# schema_8relay.net
KiCad netlist of a schematic drawn in EAGLE
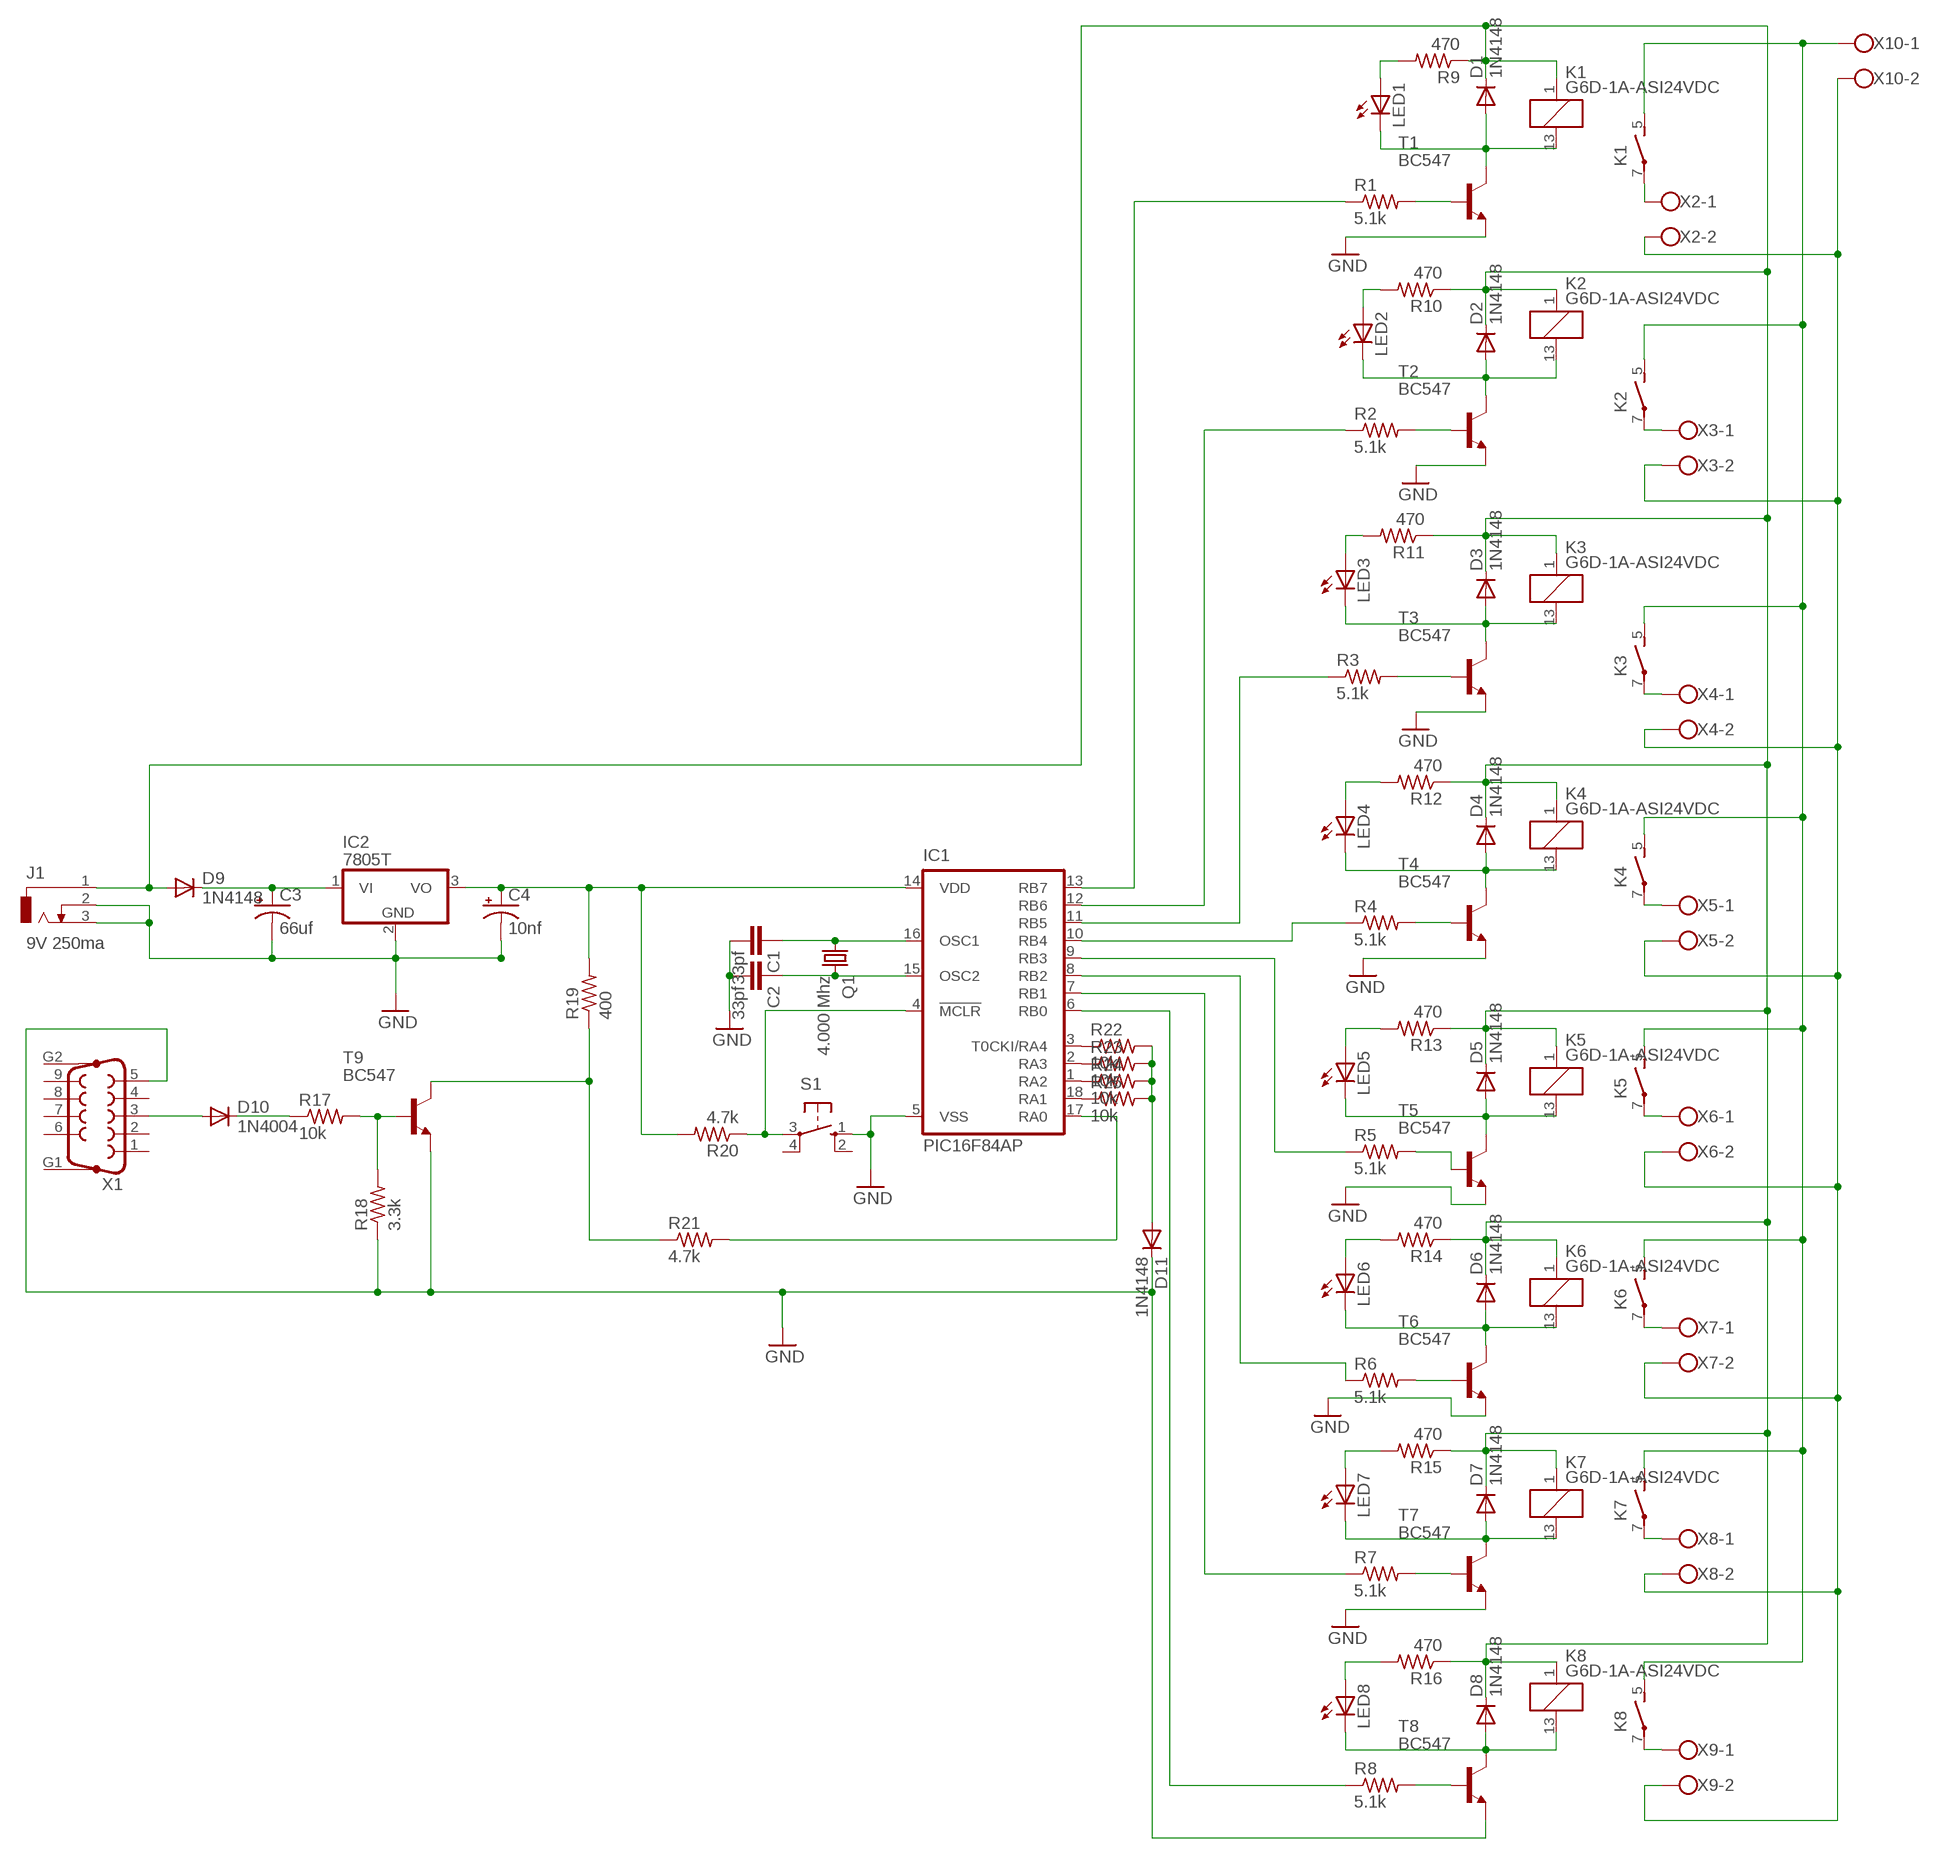
[diagram p0: schematic, sheet 1]

(export (version "E")
  (design (tool "Eeschema 10.0.6"))
  (components
    (comp (ref "C1")
      (value "33pf")
      (footprint "eagle-import:C050-024X044")
      (libsource (lib "eagle-import") (part "C-EU050-024X044"))
    )
    (comp (ref "C2")
      (value "33pf")
      (footprint "eagle-import:C050-024X044")
      (libsource (lib "eagle-import") (part "C-EU050-024X044"))
    )
    (comp (ref "C3")
      (value "66uf")
      (footprint "eagle-import:E2,5-6")
      (libsource (lib "eagle-import") (part "CPOL-USE2.5-6"))
    )
    (comp (ref "C4")
      (value "10nf")
      (footprint "eagle-import:E2,5-6")
      (libsource (lib "eagle-import") (part "CPOL-USE2.5-6"))
    )
    (comp (ref "D1")
      (value "1N4148")
      (footprint "eagle-import:DO35-10")
      (libsource (lib "eagle-import") (part "1N4148"))
    )
    (comp (ref "D2")
      (value "1N4148")
      (footprint "eagle-import:DO35-10")
      (libsource (lib "eagle-import") (part "1N4148"))
    )
    (comp (ref "D3")
      (value "1N4148")
      (footprint "eagle-import:DO35-10")
      (libsource (lib "eagle-import") (part "1N4148"))
    )
    (comp (ref "D4")
      (value "1N4148")
      (footprint "eagle-import:DO35-10")
      (libsource (lib "eagle-import") (part "1N4148"))
    )
    (comp (ref "D5")
      (value "1N4148")
      (footprint "eagle-import:DO35-10")
      (libsource (lib "eagle-import") (part "1N4148"))
    )
    (comp (ref "D6")
      (value "1N4148")
      (footprint "eagle-import:DO35-10")
      (libsource (lib "eagle-import") (part "1N4148"))
    )
    (comp (ref "D7")
      (value "1N4148")
      (footprint "eagle-import:DO35-10")
      (libsource (lib "eagle-import") (part "1N4148"))
    )
    (comp (ref "D8")
      (value "1N4148")
      (footprint "eagle-import:DO35-10")
      (libsource (lib "eagle-import") (part "1N4148"))
    )
    (comp (ref "D9")
      (value "1N4148")
      (footprint "eagle-import:DO35-10")
      (libsource (lib "eagle-import") (part "1N4148"))
    )
    (comp (ref "D10")
      (value "1N4004")
      (footprint "eagle-import:DO41-10")
      (libsource (lib "eagle-import") (part "1N4004"))
    )
    (comp (ref "D11")
      (value "1N4148")
      (footprint "eagle-import:DO35-10")
      (libsource (lib "eagle-import") (part "1N4148"))
    )
    (comp (ref "IC1")
      (value "PIC16F84AP")
      (footprint "eagle-import:DIL18")
      (libsource (lib "eagle-import") (part "PIC16F8P4A"))
    )
    (comp (ref "IC2")
      (value "7805T")
      (footprint "eagle-import:TO220H")
      (libsource (lib "eagle-import") (part "78T05"))
    )
    (comp (ref "J1")
      (value "9V 250ma")
      (footprint "eagle-import:DCJ0303")
      (libsource (lib "eagle-import") (part "DCJ0303"))
    )
    (comp (ref "K1")
      (value "G6D-1A-ASI24VDC")
      (footprint "eagle-import:G6D")
      (libsource (lib "eagle-import") (part "G6D?-1A-ASI24VDC"))
    )
    (comp (ref "K2")
      (value "G6D-1A-ASI24VDC")
      (footprint "eagle-import:G6D")
      (libsource (lib "eagle-import") (part "G6D?-1A-ASI24VDC"))
    )
    (comp (ref "K3")
      (value "G6D-1A-ASI24VDC")
      (footprint "eagle-import:G6D")
      (libsource (lib "eagle-import") (part "G6D?-1A-ASI24VDC"))
    )
    (comp (ref "K4")
      (value "G6D-1A-ASI24VDC")
      (footprint "eagle-import:G6D")
      (libsource (lib "eagle-import") (part "G6D?-1A-ASI24VDC"))
    )
    (comp (ref "K5")
      (value "G6D-1A-ASI24VDC")
      (footprint "eagle-import:G6D")
      (libsource (lib "eagle-import") (part "G6D?-1A-ASI24VDC"))
    )
    (comp (ref "K6")
      (value "G6D-1A-ASI24VDC")
      (footprint "eagle-import:G6D")
      (libsource (lib "eagle-import") (part "G6D?-1A-ASI24VDC"))
    )
    (comp (ref "K7")
      (value "G6D-1A-ASI24VDC")
      (footprint "eagle-import:G6D")
      (libsource (lib "eagle-import") (part "G6D?-1A-ASI24VDC"))
    )
    (comp (ref "K8")
      (value "G6D-1A-ASI24VDC")
      (footprint "eagle-import:G6D")
      (libsource (lib "eagle-import") (part "G6D?-1A-ASI24VDC"))
    )
    (comp (ref "LED1")
      (value "LED3MM")
      (footprint "eagle-import:LED3MM")
      (libsource (lib "eagle-import") (part "LED3MM"))
    )
    (comp (ref "LED2")
      (value "LED3MM")
      (footprint "eagle-import:LED3MM")
      (libsource (lib "eagle-import") (part "LED3MM"))
    )
    (comp (ref "LED3")
      (value "LED3MM")
      (footprint "eagle-import:LED3MM")
      (libsource (lib "eagle-import") (part "LED3MM"))
    )
    (comp (ref "LED4")
      (value "LED3MM")
      (footprint "eagle-import:LED3MM")
      (libsource (lib "eagle-import") (part "LED3MM"))
    )
    (comp (ref "LED5")
      (value "LED3MM")
      (footprint "eagle-import:LED3MM")
      (libsource (lib "eagle-import") (part "LED3MM"))
    )
    (comp (ref "LED6")
      (value "LED3MM")
      (footprint "eagle-import:LED3MM")
      (libsource (lib "eagle-import") (part "LED3MM"))
    )
    (comp (ref "LED7")
      (value "LED3MM")
      (footprint "eagle-import:LED3MM")
      (libsource (lib "eagle-import") (part "LED3MM"))
    )
    (comp (ref "LED8")
      (value "LED3MM")
      (footprint "eagle-import:LED3MM")
      (libsource (lib "eagle-import") (part "LED3MM"))
    )
    (comp (ref "Q1")
      (value "4.000 Mhz")
      (footprint "eagle-import:HC49U70")
      (libsource (lib "eagle-import") (part "CRYSTALHC49U70"))
    )
    (comp (ref "R1")
      (value "5.1k")
      (footprint "eagle-import:0204_7")
      (libsource (lib "eagle-import") (part "R-US_0204/7"))
    )
    (comp (ref "R2")
      (value "5.1k")
      (footprint "eagle-import:0204_7")
      (libsource (lib "eagle-import") (part "R-US_0204/7"))
    )
    (comp (ref "R3")
      (value "5.1k")
      (footprint "eagle-import:0204_7")
      (libsource (lib "eagle-import") (part "R-US_0204/7"))
    )
    (comp (ref "R4")
      (value "5.1k")
      (footprint "eagle-import:0204_7")
      (libsource (lib "eagle-import") (part "R-US_0204/7"))
    )
    (comp (ref "R5")
      (value "5.1k")
      (footprint "eagle-import:0204_7")
      (libsource (lib "eagle-import") (part "R-US_0204/7"))
    )
    (comp (ref "R6")
      (value "5.1k")
      (footprint "eagle-import:0204_7")
      (libsource (lib "eagle-import") (part "R-US_0204/7"))
    )
    (comp (ref "R7")
      (value "5.1k")
      (footprint "eagle-import:0204_7")
      (libsource (lib "eagle-import") (part "R-US_0204/7"))
    )
    (comp (ref "R8")
      (value "5.1k")
      (footprint "eagle-import:0204_7")
      (libsource (lib "eagle-import") (part "R-US_0204/7"))
    )
    (comp (ref "R9")
      (value "470")
      (footprint "eagle-import:0204_7")
      (libsource (lib "eagle-import") (part "R-US_0204/7"))
    )
    (comp (ref "R10")
      (value "470")
      (footprint "eagle-import:0204_7")
      (libsource (lib "eagle-import") (part "R-US_0204/7"))
    )
    (comp (ref "R11")
      (value "470")
      (footprint "eagle-import:0204_7")
      (libsource (lib "eagle-import") (part "R-US_0204/7"))
    )
    (comp (ref "R12")
      (value "470")
      (footprint "eagle-import:0204_7")
      (libsource (lib "eagle-import") (part "R-US_0204/7"))
    )
    (comp (ref "R13")
      (value "470")
      (footprint "eagle-import:0204_7")
      (libsource (lib "eagle-import") (part "R-US_0204/7"))
    )
    (comp (ref "R14")
      (value "470")
      (footprint "eagle-import:0204_7")
      (libsource (lib "eagle-import") (part "R-US_0204/7"))
    )
    (comp (ref "R15")
      (value "470")
      (footprint "eagle-import:0204_7")
      (libsource (lib "eagle-import") (part "R-US_0204/7"))
    )
    (comp (ref "R16")
      (value "470")
      (footprint "eagle-import:0204_7")
      (libsource (lib "eagle-import") (part "R-US_0204/7"))
    )
    (comp (ref "R17")
      (value "10k")
      (footprint "eagle-import:0204_7")
      (libsource (lib "eagle-import") (part "R-US_0204/7"))
    )
    (comp (ref "R18")
      (value "3.3k")
      (footprint "eagle-import:0204_7")
      (libsource (lib "eagle-import") (part "R-US_0204/7"))
    )
    (comp (ref "R19")
      (value "400")
      (footprint "eagle-import:0207_12")
      (libsource (lib "eagle-import") (part "R-US_0207/12"))
    )
    (comp (ref "R20")
      (value "4.7k")
      (footprint "eagle-import:0204_7")
      (libsource (lib "eagle-import") (part "R-US_0204/7"))
    )
    (comp (ref "R21")
      (value "4.7k")
      (footprint "eagle-import:0204_7")
      (libsource (lib "eagle-import") (part "R-US_0204/7"))
    )
    (comp (ref "R22")
      (value "10k")
      (footprint "eagle-import:0204_7")
      (libsource (lib "eagle-import") (part "R-US_0204/7"))
    )
    (comp (ref "R23")
      (value "10k")
      (footprint "eagle-import:0204_7")
      (libsource (lib "eagle-import") (part "R-US_0204/7"))
    )
    (comp (ref "R24")
      (value "10k")
      (footprint "eagle-import:0204_7")
      (libsource (lib "eagle-import") (part "R-US_0204/7"))
    )
    (comp (ref "R25")
      (value "10k")
      (footprint "eagle-import:0204_7")
      (libsource (lib "eagle-import") (part "R-US_0204/7"))
    )
    (comp (ref "S1")
      (value "10-XX")
      (footprint "eagle-import:B3F-10XX")
      (libsource (lib "eagle-import") (part "10-XX"))
    )
    (comp (ref "T1")
      (value "BC547")
      (footprint "eagle-import:TO92")
      (libsource (lib "eagle-import") (part "BC547"))
    )
    (comp (ref "T2")
      (value "BC547")
      (footprint "eagle-import:TO92")
      (libsource (lib "eagle-import") (part "BC547"))
    )
    (comp (ref "T3")
      (value "BC547")
      (footprint "eagle-import:TO92")
      (libsource (lib "eagle-import") (part "BC547"))
    )
    (comp (ref "T4")
      (value "BC547")
      (footprint "eagle-import:TO92")
      (libsource (lib "eagle-import") (part "BC547"))
    )
    (comp (ref "T5")
      (value "BC547")
      (footprint "eagle-import:TO92")
      (libsource (lib "eagle-import") (part "BC547"))
    )
    (comp (ref "T6")
      (value "BC547")
      (footprint "eagle-import:TO92")
      (libsource (lib "eagle-import") (part "BC547"))
    )
    (comp (ref "T7")
      (value "BC547")
      (footprint "eagle-import:TO92")
      (libsource (lib "eagle-import") (part "BC547"))
    )
    (comp (ref "T8")
      (value "BC547")
      (footprint "eagle-import:TO92")
      (libsource (lib "eagle-import") (part "BC547"))
    )
    (comp (ref "T9")
      (value "BC547")
      (footprint "eagle-import:TO92")
      (libsource (lib "eagle-import") (part "BC547"))
    )
    (comp (ref "X1")
      (value "F09HP")
      (footprint "eagle-import:F09HP")
      (libsource (lib "eagle-import") (part "F09HP"))
    )
    (comp (ref "X2")
      (value "W237-102")
      (footprint "eagle-import:W237-102")
      (libsource (lib "eagle-import") (part "W237-102"))
    )
    (comp (ref "X3")
      (value "W237-102")
      (footprint "eagle-import:W237-102")
      (libsource (lib "eagle-import") (part "W237-102"))
    )
    (comp (ref "X4")
      (value "W237-102")
      (footprint "eagle-import:W237-102")
      (libsource (lib "eagle-import") (part "W237-102"))
    )
    (comp (ref "X5")
      (value "W237-102")
      (footprint "eagle-import:W237-102")
      (libsource (lib "eagle-import") (part "W237-102"))
    )
    (comp (ref "X6")
      (value "W237-102")
      (footprint "eagle-import:W237-102")
      (libsource (lib "eagle-import") (part "W237-102"))
    )
    (comp (ref "X7")
      (value "W237-102")
      (footprint "eagle-import:W237-102")
      (libsource (lib "eagle-import") (part "W237-102"))
    )
    (comp (ref "X8")
      (value "W237-102")
      (footprint "eagle-import:W237-102")
      (libsource (lib "eagle-import") (part "W237-102"))
    )
    (comp (ref "X9")
      (value "W237-102")
      (footprint "eagle-import:W237-102")
      (libsource (lib "eagle-import") (part "W237-102"))
    )
    (comp (ref "X10")
      (value "W237-102")
      (footprint "eagle-import:W237-102")
      (libsource (lib "eagle-import") (part "W237-102"))
    )
  )
  (nets
    (net (code "1") (name "GND") (class "Default")
      (node (ref "C1") (pin "2") (pinfunction "2_2") (pintype "passive"))
      (node (ref "C2") (pin "2") (pinfunction "2_2") (pintype "passive"))
      (node (ref "C3") (pin "-") (pinfunction "-_-") (pintype "passive"))
      (node (ref "C4") (pin "-") (pinfunction "-_-") (pintype "passive"))
      (node (ref "D11") (pin "C") (pinfunction "C_C") (pintype "passive"))
      (node (ref "IC1") (pin "5") (pinfunction "VSS_5") (pintype "power_in"))
      (node (ref "IC2") (pin "2") (pinfunction "GND_2") (pintype "passive"))
      (node (ref "J1") (pin "2") (pinfunction "2_2") (pintype "passive"))
      (node (ref "J1") (pin "3") (pinfunction "3_3") (pintype "passive"))
      (node (ref "R18") (pin "1") (pinfunction "1_1") (pintype "passive"))
      (node (ref "S1") (pin "1") (pinfunction "S_1") (pintype "passive"))
      (node (ref "T1") (pin "1") (pinfunction "E_1") (pintype "passive"))
      (node (ref "T2") (pin "1") (pinfunction "E_1") (pintype "passive"))
      (node (ref "T3") (pin "1") (pinfunction "E_1") (pintype "passive"))
      (node (ref "T4") (pin "1") (pinfunction "E_1") (pintype "passive"))
      (node (ref "T5") (pin "1") (pinfunction "E_1") (pintype "passive"))
      (node (ref "T6") (pin "1") (pinfunction "E_1") (pintype "passive"))
      (node (ref "T7") (pin "1") (pinfunction "E_1") (pintype "passive"))
      (node (ref "T8") (pin "1") (pinfunction "E_1") (pintype "passive"))
      (node (ref "T9") (pin "1") (pinfunction "E_1") (pintype "passive"))
      (node (ref "X1") (pin "5") (pinfunction "5_5") (pintype "passive"))
    )
    (net (code "2") (name "Net-(D1-PadC)") (class "Default")
      (node (ref "D1") (pin "C") (pinfunction "C_C") (pintype "passive"))
      (node (ref "D2") (pin "C") (pinfunction "C_C") (pintype "passive"))
      (node (ref "D3") (pin "C") (pinfunction "C_C") (pintype "passive"))
      (node (ref "D4") (pin "C") (pinfunction "C_C") (pintype "passive"))
      (node (ref "D5") (pin "C") (pinfunction "C_C") (pintype "passive"))
      (node (ref "D6") (pin "C") (pinfunction "C_C") (pintype "passive"))
      (node (ref "D7") (pin "C") (pinfunction "C_C") (pintype "passive"))
      (node (ref "D8") (pin "C") (pinfunction "C_C") (pintype "passive"))
      (node (ref "D9") (pin "A") (pinfunction "A_A") (pintype "passive"))
      (node (ref "J1") (pin "1") (pinfunction "1_1") (pintype "passive"))
      (node (ref "K1") (pin "1") (pinfunction "1_1") (pintype "passive"))
      (node (ref "K2") (pin "1") (pinfunction "1_1") (pintype "passive"))
      (node (ref "K3") (pin "1") (pinfunction "1_1") (pintype "passive"))
      (node (ref "K4") (pin "1") (pinfunction "1_1") (pintype "passive"))
      (node (ref "K5") (pin "1") (pinfunction "1_1") (pintype "passive"))
      (node (ref "K6") (pin "1") (pinfunction "1_1") (pintype "passive"))
      (node (ref "K7") (pin "1") (pinfunction "1_1") (pintype "passive"))
      (node (ref "K8") (pin "1") (pinfunction "1_1") (pintype "passive"))
      (node (ref "R10") (pin "1") (pinfunction "1_1") (pintype "passive"))
      (node (ref "R11") (pin "1") (pinfunction "1_1") (pintype "passive"))
      (node (ref "R12") (pin "1") (pinfunction "1_1") (pintype "passive"))
      (node (ref "R13") (pin "1") (pinfunction "1_1") (pintype "passive"))
      (node (ref "R14") (pin "1") (pinfunction "1_1") (pintype "passive"))
      (node (ref "R15") (pin "1") (pinfunction "1_1") (pintype "passive"))
      (node (ref "R16") (pin "1") (pinfunction "1_1") (pintype "passive"))
      (node (ref "R9") (pin "1") (pinfunction "1_1") (pintype "passive"))
    )
    (net (code "3") (name "Net-(D10-PadA)") (class "Default")
      (node (ref "D10") (pin "A") (pinfunction "A_A") (pintype "passive"))
      (node (ref "X1") (pin "3") (pinfunction "3_3") (pintype "passive"))
    )
    (net (code "4") (name "Net-(D10-PadC)") (class "Default")
      (node (ref "D10") (pin "C") (pinfunction "C_C") (pintype "passive"))
      (node (ref "R17") (pin "1") (pinfunction "1_1") (pintype "passive"))
    )
    (net (code "5") (name "Net-(D11-PadA)") (class "Default")
      (node (ref "D11") (pin "A") (pinfunction "A_A") (pintype "passive"))
      (node (ref "R22") (pin "2") (pinfunction "2_2") (pintype "passive"))
      (node (ref "R23") (pin "2") (pinfunction "2_2") (pintype "passive"))
      (node (ref "R24") (pin "2") (pinfunction "2_2") (pintype "passive"))
      (node (ref "R25") (pin "2") (pinfunction "2_2") (pintype "passive"))
    )
    (net (code "6") (name "Net-(IC1-OSC1)") (class "Default")
      (node (ref "C1") (pin "1") (pinfunction "1_1") (pintype "passive"))
      (node (ref "IC1") (pin "16") (pinfunction "OSC1_16") (pintype "input"))
      (node (ref "Q1") (pin "1") (pinfunction "1_1") (pintype "passive"))
    )
    (net (code "7") (name "Net-(IC1-OSC2)") (class "Default")
      (node (ref "C2") (pin "1") (pinfunction "1_1") (pintype "passive"))
      (node (ref "IC1") (pin "15") (pinfunction "OSC2_15") (pintype "output"))
      (node (ref "Q1") (pin "2") (pinfunction "2_2") (pintype "passive"))
    )
    (net (code "8") (name "Net-(IC1-RA0)") (class "Default")
      (node (ref "IC1") (pin "17") (pinfunction "RA0_17") (pintype "bidirectional"))
      (node (ref "R21") (pin "2") (pinfunction "2_2") (pintype "passive"))
    )
    (net (code "9") (name "Net-(IC1-RA1)") (class "Default")
      (node (ref "IC1") (pin "18") (pinfunction "RA1_18") (pintype "bidirectional"))
      (node (ref "R25") (pin "1") (pinfunction "1_1") (pintype "passive"))
    )
    (net (code "10") (name "Net-(IC1-RA2)") (class "Default")
      (node (ref "IC1") (pin "1") (pinfunction "RA2_1") (pintype "bidirectional"))
      (node (ref "R24") (pin "1") (pinfunction "1_1") (pintype "passive"))
    )
    (net (code "11") (name "Net-(IC1-RA3)") (class "Default")
      (node (ref "IC1") (pin "2") (pinfunction "RA3_2") (pintype "bidirectional"))
      (node (ref "R23") (pin "1") (pinfunction "1_1") (pintype "passive"))
    )
    (net (code "12") (name "Net-(IC1-RB0)") (class "Default")
      (node (ref "IC1") (pin "6") (pinfunction "RB0_6") (pintype "bidirectional"))
      (node (ref "R8") (pin "1") (pinfunction "1_1") (pintype "passive"))
    )
    (net (code "13") (name "Net-(IC1-RB1)") (class "Default")
      (node (ref "IC1") (pin "7") (pinfunction "RB1_7") (pintype "bidirectional"))
      (node (ref "R7") (pin "1") (pinfunction "1_1") (pintype "passive"))
    )
    (net (code "14") (name "Net-(IC1-RB2)") (class "Default")
      (node (ref "IC1") (pin "8") (pinfunction "RB2_8") (pintype "bidirectional"))
      (node (ref "R6") (pin "1") (pinfunction "1_1") (pintype "passive"))
    )
    (net (code "15") (name "Net-(IC1-RB3)") (class "Default")
      (node (ref "IC1") (pin "9") (pinfunction "RB3_9") (pintype "bidirectional"))
      (node (ref "R5") (pin "1") (pinfunction "1_1") (pintype "passive"))
    )
    (net (code "16") (name "Net-(IC1-RB4)") (class "Default")
      (node (ref "IC1") (pin "10") (pinfunction "RB4_10") (pintype "bidirectional"))
      (node (ref "R4") (pin "1") (pinfunction "1_1") (pintype "passive"))
    )
    (net (code "17") (name "Net-(IC1-RB5)") (class "Default")
      (node (ref "IC1") (pin "11") (pinfunction "RB5_11") (pintype "bidirectional"))
      (node (ref "R3") (pin "1") (pinfunction "1_1") (pintype "passive"))
    )
    (net (code "18") (name "Net-(IC1-RB6)") (class "Default")
      (node (ref "IC1") (pin "12") (pinfunction "RB6_12") (pintype "bidirectional"))
      (node (ref "R2") (pin "1") (pinfunction "1_1") (pintype "passive"))
    )
    (net (code "19") (name "Net-(IC1-RB7)") (class "Default")
      (node (ref "IC1") (pin "13") (pinfunction "RB7_13") (pintype "bidirectional"))
      (node (ref "R1") (pin "1") (pinfunction "1_1") (pintype "passive"))
    )
    (net (code "20") (name "Net-(IC1-T0CKI{slash}RA4)") (class "Default")
      (node (ref "IC1") (pin "3") (pinfunction "T0CKI/RA4_3") (pintype "bidirectional"))
      (node (ref "R22") (pin "1") (pinfunction "1_1") (pintype "passive"))
    )
    (net (code "21") (name "Net-(IC1-VDD)") (class "Default")
      (node (ref "C4") (pin "+") (pinfunction "+_+") (pintype "passive"))
      (node (ref "IC1") (pin "14") (pinfunction "VDD_14") (pintype "power_in"))
      (node (ref "IC2") (pin "3") (pinfunction "VO_3") (pintype "passive"))
      (node (ref "R19") (pin "2") (pinfunction "2_2") (pintype "passive"))
      (node (ref "R20") (pin "2") (pinfunction "2_2") (pintype "passive"))
    )
    (net (code "22") (name "Net-(IC1-~{MCLR})") (class "Default")
      (node (ref "IC1") (pin "4") (pinfunction "~{MCLR}_4") (pintype "input"))
      (node (ref "R20") (pin "1") (pinfunction "1_1") (pintype "passive"))
      (node (ref "S1") (pin "3") (pinfunction "P_3") (pintype "passive"))
    )
    (net (code "23") (name "Net-(IC2-VI)") (class "Default")
      (node (ref "C3") (pin "+") (pinfunction "+_+") (pintype "passive"))
      (node (ref "D9") (pin "C") (pinfunction "C_C") (pintype "passive"))
      (node (ref "IC2") (pin "1") (pinfunction "VI_1") (pintype "input"))
    )
    (net (code "24") (name "Net-(K1A-2)") (class "Default")
      (node (ref "D1") (pin "A") (pinfunction "A_A") (pintype "passive"))
      (node (ref "K1") (pin "13") (pinfunction "2_13") (pintype "passive"))
      (node (ref "LED1") (pin "K") (pinfunction "C_K") (pintype "passive"))
      (node (ref "T1") (pin "3") (pinfunction "C_3") (pintype "passive"))
    )
    (net (code "25") (name "Net-(K1B-P)") (class "Default")
      (node (ref "K1") (pin "7") (pinfunction "P_7") (pintype "passive"))
      (node (ref "X2") (pin "1") (pinfunction "KL_1") (pintype "passive"))
    )
    (net (code "26") (name "Net-(K1B-S)") (class "Default")
      (node (ref "K1") (pin "5") (pinfunction "S_5") (pintype "passive"))
      (node (ref "K2") (pin "5") (pinfunction "S_5") (pintype "passive"))
      (node (ref "K3") (pin "5") (pinfunction "S_5") (pintype "passive"))
      (node (ref "K4") (pin "5") (pinfunction "S_5") (pintype "passive"))
      (node (ref "K5") (pin "5") (pinfunction "S_5") (pintype "passive"))
      (node (ref "K6") (pin "5") (pinfunction "S_5") (pintype "passive"))
      (node (ref "K7") (pin "5") (pinfunction "S_5") (pintype "passive"))
      (node (ref "K8") (pin "5") (pinfunction "S_5") (pintype "passive"))
      (node (ref "X10") (pin "1") (pinfunction "KL_1") (pintype "passive"))
    )
    (net (code "27") (name "Net-(K2A-2)") (class "Default")
      (node (ref "D2") (pin "A") (pinfunction "A_A") (pintype "passive"))
      (node (ref "K2") (pin "13") (pinfunction "2_13") (pintype "passive"))
      (node (ref "LED2") (pin "K") (pinfunction "C_K") (pintype "passive"))
      (node (ref "T2") (pin "3") (pinfunction "C_3") (pintype "passive"))
    )
    (net (code "28") (name "Net-(K2B-P)") (class "Default")
      (node (ref "K2") (pin "7") (pinfunction "P_7") (pintype "passive"))
      (node (ref "X3") (pin "1") (pinfunction "KL_1") (pintype "passive"))
    )
    (net (code "29") (name "Net-(K3A-2)") (class "Default")
      (node (ref "D3") (pin "A") (pinfunction "A_A") (pintype "passive"))
      (node (ref "K3") (pin "13") (pinfunction "2_13") (pintype "passive"))
      (node (ref "LED3") (pin "K") (pinfunction "C_K") (pintype "passive"))
      (node (ref "T3") (pin "3") (pinfunction "C_3") (pintype "passive"))
    )
    (net (code "30") (name "Net-(K3B-P)") (class "Default")
      (node (ref "K3") (pin "7") (pinfunction "P_7") (pintype "passive"))
      (node (ref "X4") (pin "1") (pinfunction "KL_1") (pintype "passive"))
    )
    (net (code "31") (name "Net-(K4A-2)") (class "Default")
      (node (ref "D4") (pin "A") (pinfunction "A_A") (pintype "passive"))
      (node (ref "K4") (pin "13") (pinfunction "2_13") (pintype "passive"))
      (node (ref "LED4") (pin "K") (pinfunction "C_K") (pintype "passive"))
      (node (ref "T4") (pin "3") (pinfunction "C_3") (pintype "passive"))
    )
    (net (code "32") (name "Net-(K4B-P)") (class "Default")
      (node (ref "K4") (pin "7") (pinfunction "P_7") (pintype "passive"))
      (node (ref "X5") (pin "1") (pinfunction "KL_1") (pintype "passive"))
    )
    (net (code "33") (name "Net-(K5A-2)") (class "Default")
      (node (ref "D5") (pin "A") (pinfunction "A_A") (pintype "passive"))
      (node (ref "K5") (pin "13") (pinfunction "2_13") (pintype "passive"))
      (node (ref "LED5") (pin "K") (pinfunction "C_K") (pintype "passive"))
      (node (ref "T5") (pin "3") (pinfunction "C_3") (pintype "passive"))
    )
    (net (code "34") (name "Net-(K5B-P)") (class "Default")
      (node (ref "K5") (pin "7") (pinfunction "P_7") (pintype "passive"))
      (node (ref "X6") (pin "1") (pinfunction "KL_1") (pintype "passive"))
    )
    (net (code "35") (name "Net-(K6A-2)") (class "Default")
      (node (ref "D6") (pin "A") (pinfunction "A_A") (pintype "passive"))
      (node (ref "K6") (pin "13") (pinfunction "2_13") (pintype "passive"))
      (node (ref "LED6") (pin "K") (pinfunction "C_K") (pintype "passive"))
      (node (ref "T6") (pin "3") (pinfunction "C_3") (pintype "passive"))
    )
    (net (code "36") (name "Net-(K6B-P)") (class "Default")
      (node (ref "K6") (pin "7") (pinfunction "P_7") (pintype "passive"))
      (node (ref "X7") (pin "1") (pinfunction "KL_1") (pintype "passive"))
    )
    (net (code "37") (name "Net-(K7A-2)") (class "Default")
      (node (ref "D7") (pin "A") (pinfunction "A_A") (pintype "passive"))
      (node (ref "K7") (pin "13") (pinfunction "2_13") (pintype "passive"))
      (node (ref "LED7") (pin "K") (pinfunction "C_K") (pintype "passive"))
      (node (ref "T7") (pin "3") (pinfunction "C_3") (pintype "passive"))
    )
    (net (code "38") (name "Net-(K7B-P)") (class "Default")
      (node (ref "K7") (pin "7") (pinfunction "P_7") (pintype "passive"))
      (node (ref "X8") (pin "1") (pinfunction "KL_1") (pintype "passive"))
    )
    (net (code "39") (name "Net-(K8A-2)") (class "Default")
      (node (ref "D8") (pin "A") (pinfunction "A_A") (pintype "passive"))
      (node (ref "K8") (pin "13") (pinfunction "2_13") (pintype "passive"))
      (node (ref "LED8") (pin "K") (pinfunction "C_K") (pintype "passive"))
      (node (ref "T8") (pin "3") (pinfunction "C_3") (pintype "passive"))
    )
    (net (code "40") (name "Net-(K8B-P)") (class "Default")
      (node (ref "K8") (pin "7") (pinfunction "P_7") (pintype "passive"))
      (node (ref "X9") (pin "1") (pinfunction "KL_1") (pintype "passive"))
    )
    (net (code "41") (name "Net-(LED1-PadA)") (class "Default")
      (node (ref "LED1") (pin "A") (pinfunction "A_A") (pintype "passive"))
      (node (ref "R9") (pin "2") (pinfunction "2_2") (pintype "passive"))
    )
    (net (code "42") (name "Net-(LED2-PadA)") (class "Default")
      (node (ref "LED2") (pin "A") (pinfunction "A_A") (pintype "passive"))
      (node (ref "R10") (pin "2") (pinfunction "2_2") (pintype "passive"))
    )
    (net (code "43") (name "Net-(LED3-PadA)") (class "Default")
      (node (ref "LED3") (pin "A") (pinfunction "A_A") (pintype "passive"))
      (node (ref "R11") (pin "2") (pinfunction "2_2") (pintype "passive"))
    )
    (net (code "44") (name "Net-(LED4-PadA)") (class "Default")
      (node (ref "LED4") (pin "A") (pinfunction "A_A") (pintype "passive"))
      (node (ref "R12") (pin "2") (pinfunction "2_2") (pintype "passive"))
    )
    (net (code "45") (name "Net-(LED5-PadA)") (class "Default")
      (node (ref "LED5") (pin "A") (pinfunction "A_A") (pintype "passive"))
      (node (ref "R13") (pin "2") (pinfunction "2_2") (pintype "passive"))
    )
    (net (code "46") (name "Net-(LED6-PadA)") (class "Default")
      (node (ref "LED6") (pin "A") (pinfunction "A_A") (pintype "passive"))
      (node (ref "R14") (pin "2") (pinfunction "2_2") (pintype "passive"))
    )
    (net (code "47") (name "Net-(LED7-PadA)") (class "Default")
      (node (ref "LED7") (pin "A") (pinfunction "A_A") (pintype "passive"))
      (node (ref "R15") (pin "2") (pinfunction "2_2") (pintype "passive"))
    )
    (net (code "48") (name "Net-(LED8-PadA)") (class "Default")
      (node (ref "LED8") (pin "A") (pinfunction "A_A") (pintype "passive"))
      (node (ref "R16") (pin "2") (pinfunction "2_2") (pintype "passive"))
    )
    (net (code "49") (name "Net-(T1-B)") (class "Default")
      (node (ref "R1") (pin "2") (pinfunction "2_2") (pintype "passive"))
      (node (ref "T1") (pin "2") (pinfunction "B_2") (pintype "passive"))
    )
    (net (code "50") (name "Net-(T2-B)") (class "Default")
      (node (ref "R2") (pin "2") (pinfunction "2_2") (pintype "passive"))
      (node (ref "T2") (pin "2") (pinfunction "B_2") (pintype "passive"))
    )
    (net (code "51") (name "Net-(T3-B)") (class "Default")
      (node (ref "R3") (pin "2") (pinfunction "2_2") (pintype "passive"))
      (node (ref "T3") (pin "2") (pinfunction "B_2") (pintype "passive"))
    )
    (net (code "52") (name "Net-(T4-B)") (class "Default")
      (node (ref "R4") (pin "2") (pinfunction "2_2") (pintype "passive"))
      (node (ref "T4") (pin "2") (pinfunction "B_2") (pintype "passive"))
    )
    (net (code "53") (name "Net-(T5-B)") (class "Default")
      (node (ref "R5") (pin "2") (pinfunction "2_2") (pintype "passive"))
      (node (ref "T5") (pin "2") (pinfunction "B_2") (pintype "passive"))
    )
    (net (code "54") (name "Net-(T6-B)") (class "Default")
      (node (ref "R6") (pin "2") (pinfunction "2_2") (pintype "passive"))
      (node (ref "T6") (pin "2") (pinfunction "B_2") (pintype "passive"))
    )
    (net (code "55") (name "Net-(T7-B)") (class "Default")
      (node (ref "R7") (pin "2") (pinfunction "2_2") (pintype "passive"))
      (node (ref "T7") (pin "2") (pinfunction "B_2") (pintype "passive"))
    )
    (net (code "56") (name "Net-(T8-B)") (class "Default")
      (node (ref "R8") (pin "2") (pinfunction "2_2") (pintype "passive"))
      (node (ref "T8") (pin "2") (pinfunction "B_2") (pintype "passive"))
    )
    (net (code "57") (name "Net-(T9-B)") (class "Default")
      (node (ref "R17") (pin "2") (pinfunction "2_2") (pintype "passive"))
      (node (ref "R18") (pin "2") (pinfunction "2_2") (pintype "passive"))
      (node (ref "T9") (pin "2") (pinfunction "B_2") (pintype "passive"))
    )
    (net (code "58") (name "Net-(T9-C)") (class "Default")
      (node (ref "R19") (pin "1") (pinfunction "1_1") (pintype "passive"))
      (node (ref "R21") (pin "1") (pinfunction "1_1") (pintype "passive"))
      (node (ref "T9") (pin "3") (pinfunction "C_3") (pintype "passive"))
    )
    (net (code "59") (name "Net-(X10B-KL)") (class "Default")
      (node (ref "X10") (pin "2") (pinfunction "KL_2") (pintype "passive"))
      (node (ref "X2") (pin "2") (pinfunction "KL_2") (pintype "passive"))
      (node (ref "X3") (pin "2") (pinfunction "KL_2") (pintype "passive"))
      (node (ref "X4") (pin "2") (pinfunction "KL_2") (pintype "passive"))
      (node (ref "X5") (pin "2") (pinfunction "KL_2") (pintype "passive"))
      (node (ref "X6") (pin "2") (pinfunction "KL_2") (pintype "passive"))
      (node (ref "X7") (pin "2") (pinfunction "KL_2") (pintype "passive"))
      (node (ref "X8") (pin "2") (pinfunction "KL_2") (pintype "passive"))
      (node (ref "X9") (pin "2") (pinfunction "KL_2") (pintype "passive"))
    )
    (net (code "60") (name "unconnected-(S1-P1-Pad4)") (class "Default")
      (node (ref "S1") (pin "4") (pinfunction "P1_4") (pintype "passive"))
    )
    (net (code "61") (name "unconnected-(S1-S1-Pad2)") (class "Default")
      (node (ref "S1") (pin "2") (pinfunction "S1_2") (pintype "passive"))
    )
    (net (code "62") (name "unconnected-(X1-Pad1)") (class "Default")
      (node (ref "X1") (pin "1") (pinfunction "1_1") (pintype "passive"))
    )
    (net (code "63") (name "unconnected-(X1-Pad2)") (class "Default")
      (node (ref "X1") (pin "2") (pinfunction "2_2") (pintype "passive"))
    )
    (net (code "64") (name "unconnected-(X1-Pad4)") (class "Default")
      (node (ref "X1") (pin "4") (pinfunction "4_4") (pintype "passive"))
    )
    (net (code "65") (name "unconnected-(X1-Pad6)") (class "Default")
      (node (ref "X1") (pin "6") (pinfunction "6_6") (pintype "passive"))
    )
    (net (code "66") (name "unconnected-(X1-Pad7)") (class "Default")
      (node (ref "X1") (pin "7") (pinfunction "7_7") (pintype "passive"))
    )
    (net (code "67") (name "unconnected-(X1-Pad8)") (class "Default")
      (node (ref "X1") (pin "8") (pinfunction "8_8") (pintype "passive"))
    )
    (net (code "68") (name "unconnected-(X1-Pad9)") (class "Default")
      (node (ref "X1") (pin "9") (pinfunction "9_9") (pintype "passive"))
    )
    (net (code "69") (name "unconnected-(X1-PadG1)") (class "Default")
      (node (ref "X1") (pin "G1") (pinfunction "G1_G1") (pintype "passive"))
    )
    (net (code "70") (name "unconnected-(X1-PadG2)") (class "Default")
      (node (ref "X1") (pin "G2") (pinfunction "G2_G2") (pintype "passive"))
    )
  )
)
